# Paulo_V2.net
KiCad netlist of a schematic drawn in EAGLE
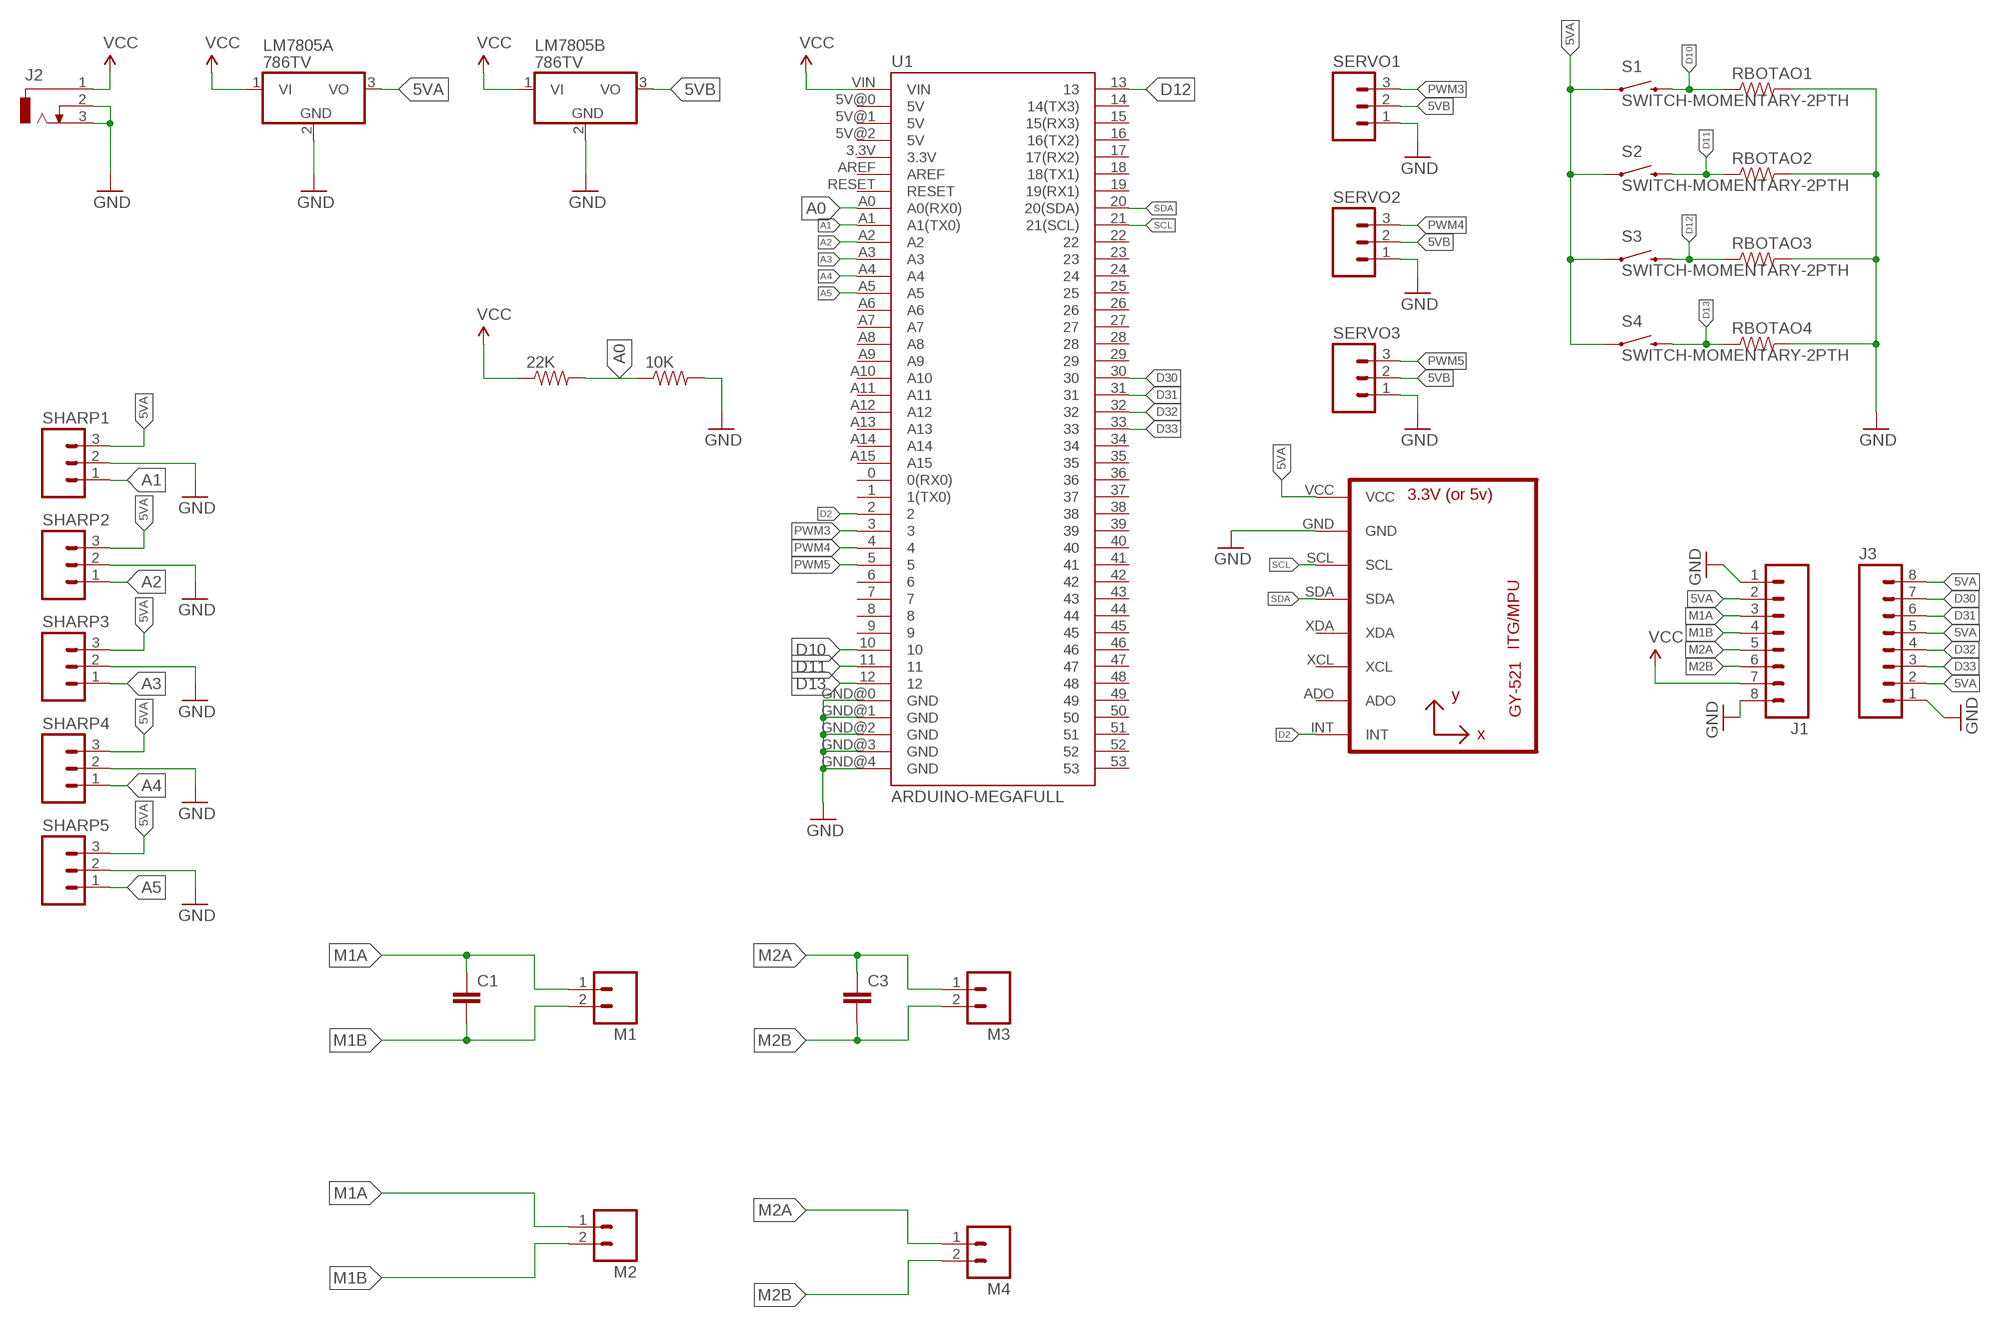
[diagram p0: schematic, sheet 1]

(export (version "E")
  (design (tool "Eeschema 10.0.6"))
  (components
    (comp (ref "10K")
      (value "RESISTOREZ")
      (footprint "eagle-import:AXIAL-0.3EZ")
      (libsource (lib "eagle-import") (part "RESISTOREZ"))
    )
    (comp (ref "22K")
      (value "RESISTOREZ")
      (footprint "eagle-import:AXIAL-0.3EZ")
      (libsource (lib "eagle-import") (part "RESISTOREZ"))
    )
    (comp (ref "C1")
      (value "CAPEZ")
      (footprint "eagle-import:CAP-PTH-SMALLEZ")
      (libsource (lib "eagle-import") (part "CAPEZ"))
    )
    (comp (ref "C3")
      (value "CAPEZ")
      (footprint "eagle-import:CAP-PTH-SMALLEZ")
      (libsource (lib "eagle-import") (part "CAPEZ"))
    )
    (comp (ref "J1")
      (value "M08NO_SILK")
      (footprint "eagle-import:1X08_PIN1_NO_SILK")
      (libsource (lib "eagle-import") (part "M08NO_SILK"))
    )
    (comp (ref "J2")
      (value "DCJ0303")
      (footprint "eagle-import:DCJ0303")
      (libsource (lib "eagle-import") (part "DCJ0303"))
    )
    (comp (ref "J3")
      (value "M08NO_SILK")
      (footprint "eagle-import:1X08_PIN1_NO_SILK")
      (libsource (lib "eagle-import") (part "M08NO_SILK"))
    )
    (comp (ref "LM7805A")
      (value "786TV")
      (footprint "eagle-import:TO220V")
      (libsource (lib "eagle-import") (part "78TV6"))
    )
    (comp (ref "LM7805B")
      (value "786TV")
      (footprint "eagle-import:TO220V")
      (libsource (lib "eagle-import") (part "78TV6"))
    )
    (comp (ref "M1")
      (value "M02JST-PTH-VERT")
      (footprint "eagle-import:JST-2-PTH-VERT")
      (libsource (lib "eagle-import") (part "M02JST-PTH-VERT"))
    )
    (comp (ref "M2")
      (value "M02JST-PTH-VERT")
      (footprint "eagle-import:JST-2-PTH-VERT")
      (libsource (lib "eagle-import") (part "M02JST-PTH-VERT"))
    )
    (comp (ref "M3")
      (value "M02JST-PTH-VERT")
      (footprint "eagle-import:JST-2-PTH-VERT")
      (libsource (lib "eagle-import") (part "M02JST-PTH-VERT"))
    )
    (comp (ref "M4")
      (value "M02JST-PTH-VERT")
      (footprint "eagle-import:JST-2-PTH-VERT")
      (libsource (lib "eagle-import") (part "M02JST-PTH-VERT"))
    )
    (comp (ref "RBOTAO1")
      (value "RESISTOREZ")
      (footprint "eagle-import:AXIAL-0.3EZ")
      (libsource (lib "eagle-import") (part "RESISTOREZ"))
    )
    (comp (ref "RBOTAO2")
      (value "RESISTOREZ")
      (footprint "eagle-import:AXIAL-0.3EZ")
      (libsource (lib "eagle-import") (part "RESISTOREZ"))
    )
    (comp (ref "RBOTAO3")
      (value "RESISTOREZ")
      (footprint "eagle-import:AXIAL-0.3EZ")
      (libsource (lib "eagle-import") (part "RESISTOREZ"))
    )
    (comp (ref "RBOTAO4")
      (value "RESISTOREZ")
      (footprint "eagle-import:AXIAL-0.3EZ")
      (libsource (lib "eagle-import") (part "RESISTOREZ"))
    )
    (comp (ref "S1")
      (value "SWITCH-MOMENTARY-2PTH")
      (footprint "eagle-import:TACTILE-PTH")
      (libsource (lib "eagle-import") (part "SWITCH-MOMENTARY-2PTH"))
    )
    (comp (ref "S2")
      (value "SWITCH-MOMENTARY-2PTH")
      (footprint "eagle-import:TACTILE-PTH")
      (libsource (lib "eagle-import") (part "SWITCH-MOMENTARY-2PTH"))
    )
    (comp (ref "S3")
      (value "SWITCH-MOMENTARY-2PTH")
      (footprint "eagle-import:TACTILE-PTH")
      (libsource (lib "eagle-import") (part "SWITCH-MOMENTARY-2PTH"))
    )
    (comp (ref "S4")
      (value "SWITCH-MOMENTARY-2PTH")
      (footprint "eagle-import:TACTILE-PTH")
      (libsource (lib "eagle-import") (part "SWITCH-MOMENTARY-2PTH"))
    )
    (comp (ref "SERVO1")
      (value "M03LONGPADS")
      (footprint "eagle-import:1X03_LONGPADS")
      (libsource (lib "eagle-import") (part "M03LONGPADS"))
    )
    (comp (ref "SERVO2")
      (value "M03LONGPADS")
      (footprint "eagle-import:1X03_LONGPADS")
      (libsource (lib "eagle-import") (part "M03LONGPADS"))
    )
    (comp (ref "SERVO3")
      (value "M03LONGPADS")
      (footprint "eagle-import:1X03_LONGPADS")
      (libsource (lib "eagle-import") (part "M03LONGPADS"))
    )
    (comp (ref "SHARP1")
      (value "M03LONGPADS")
      (footprint "eagle-import:1X03_LONGPADS")
      (libsource (lib "eagle-import") (part "M03LONGPADS"))
    )
    (comp (ref "SHARP2")
      (value "M03LONGPADS")
      (footprint "eagle-import:1X03_LONGPADS")
      (libsource (lib "eagle-import") (part "M03LONGPADS"))
    )
    (comp (ref "SHARP3")
      (value "M03LONGPADS")
      (footprint "eagle-import:1X03_LONGPADS")
      (libsource (lib "eagle-import") (part "M03LONGPADS"))
    )
    (comp (ref "SHARP4")
      (value "M03LONGPADS")
      (footprint "eagle-import:1X03_LONGPADS")
      (libsource (lib "eagle-import") (part "M03LONGPADS"))
    )
    (comp (ref "SHARP5")
      (value "M03LONGPADS")
      (footprint "eagle-import:1X03_LONGPADS")
      (libsource (lib "eagle-import") (part "M03LONGPADS"))
    )
    (comp (ref "U1")
      (value "ARDUINO-MEGAFULL")
      (footprint "eagle-import:ARDUINO_MEGA")
      (libsource (lib "eagle-import") (part "ARDUINO-MEGAFULL"))
    )
    (comp (ref "U2")
      (value "GY-521MPU6050")
      (footprint "eagle-import:GY-521")
      (libsource (lib "eagle-import") (part "GY-521MPU6050"))
    )
  )
  (nets
    (net (code "1") (name "5VA") (class "Default")
      (node (ref "J1") (pin "2") (pinfunction "2_2") (pintype "passive"))
      (node (ref "J3") (pin "2") (pinfunction "2_2") (pintype "passive"))
      (node (ref "J3") (pin "5") (pinfunction "5_5") (pintype "passive"))
      (node (ref "J3") (pin "8") (pinfunction "8_8") (pintype "passive"))
      (node (ref "LM7805A") (pin "3") (pinfunction "VO_3") (pintype "passive"))
      (node (ref "S1") (pin "1") (pinfunction "1_1") (pintype "passive"))
      (node (ref "S2") (pin "1") (pinfunction "1_1") (pintype "passive"))
      (node (ref "S3") (pin "1") (pinfunction "1_1") (pintype "passive"))
      (node (ref "S4") (pin "1") (pinfunction "1_1") (pintype "passive"))
      (node (ref "SHARP1") (pin "3") (pinfunction "3_3") (pintype "passive"))
      (node (ref "SHARP2") (pin "3") (pinfunction "3_3") (pintype "passive"))
      (node (ref "SHARP3") (pin "3") (pinfunction "3_3") (pintype "passive"))
      (node (ref "SHARP4") (pin "3") (pinfunction "3_3") (pintype "passive"))
      (node (ref "SHARP5") (pin "3") (pinfunction "3_3") (pintype "passive"))
      (node (ref "U2") (pin "VCC") (pinfunction "VCC_VCC") (pintype "bidirectional"))
    )
    (net (code "2") (name "5VB") (class "Default")
      (node (ref "LM7805B") (pin "3") (pinfunction "VO_3") (pintype "passive"))
      (node (ref "SERVO1") (pin "2") (pinfunction "2_2") (pintype "passive"))
      (node (ref "SERVO2") (pin "2") (pinfunction "2_2") (pintype "passive"))
      (node (ref "SERVO3") (pin "2") (pinfunction "2_2") (pintype "passive"))
    )
    (net (code "3") (name "A0") (class "Default")
      (node (ref "10K") (pin "P$1") (pinfunction "1_P$1") (pintype "passive"))
      (node (ref "22K") (pin "P$2") (pinfunction "2_P$2") (pintype "passive"))
      (node (ref "U1") (pin "A0") (pinfunction "A0(RX0)_A0") (pintype "bidirectional"))
    )
    (net (code "4") (name "A1") (class "Default")
      (node (ref "SHARP1") (pin "1") (pinfunction "1_1") (pintype "passive"))
      (node (ref "U1") (pin "A1") (pinfunction "A1(TX0)_A1") (pintype "bidirectional"))
    )
    (net (code "5") (name "A2") (class "Default")
      (node (ref "SHARP2") (pin "1") (pinfunction "1_1") (pintype "passive"))
      (node (ref "U1") (pin "A2") (pinfunction "A2_A2") (pintype "bidirectional"))
    )
    (net (code "6") (name "A3") (class "Default")
      (node (ref "SHARP3") (pin "1") (pinfunction "1_1") (pintype "passive"))
      (node (ref "U1") (pin "A3") (pinfunction "A3_A3") (pintype "bidirectional"))
    )
    (net (code "7") (name "A4") (class "Default")
      (node (ref "SHARP4") (pin "1") (pinfunction "1_1") (pintype "passive"))
      (node (ref "U1") (pin "A4") (pinfunction "A4_A4") (pintype "bidirectional"))
    )
    (net (code "8") (name "A5") (class "Default")
      (node (ref "SHARP5") (pin "1") (pinfunction "1_1") (pintype "passive"))
      (node (ref "U1") (pin "A5") (pinfunction "A5_A5") (pintype "bidirectional"))
    )
    (net (code "9") (name "D2") (class "Default")
      (node (ref "U1") (pin "2") (pinfunction "2_2") (pintype "bidirectional"))
      (node (ref "U2") (pin "INT") (pinfunction "INT_INT") (pintype "bidirectional"))
    )
    (net (code "10") (name "D10") (class "Default")
      (node (ref "RBOTAO1") (pin "P$1") (pinfunction "1_P$1") (pintype "passive"))
      (node (ref "S1") (pin "3") (pinfunction "2_3") (pintype "passive"))
      (node (ref "U1") (pin "10") (pinfunction "10_10") (pintype "bidirectional"))
    )
    (net (code "11") (name "D11") (class "Default")
      (node (ref "RBOTAO2") (pin "P$1") (pinfunction "1_P$1") (pintype "passive"))
      (node (ref "S2") (pin "3") (pinfunction "2_3") (pintype "passive"))
      (node (ref "U1") (pin "11") (pinfunction "11_11") (pintype "bidirectional"))
    )
    (net (code "12") (name "D12") (class "Default")
      (node (ref "RBOTAO3") (pin "P$1") (pinfunction "1_P$1") (pintype "passive"))
      (node (ref "S3") (pin "3") (pinfunction "2_3") (pintype "passive"))
      (node (ref "U1") (pin "13") (pinfunction "13_13") (pintype "bidirectional"))
    )
    (net (code "13") (name "D13") (class "Default")
      (node (ref "RBOTAO4") (pin "P$1") (pinfunction "1_P$1") (pintype "passive"))
      (node (ref "S4") (pin "3") (pinfunction "2_3") (pintype "passive"))
      (node (ref "U1") (pin "12") (pinfunction "12_12") (pintype "bidirectional"))
    )
    (net (code "14") (name "D30") (class "Default")
      (node (ref "J3") (pin "7") (pinfunction "7_7") (pintype "passive"))
      (node (ref "U1") (pin "30") (pinfunction "30_30") (pintype "bidirectional"))
    )
    (net (code "15") (name "D31") (class "Default")
      (node (ref "J3") (pin "6") (pinfunction "6_6") (pintype "passive"))
      (node (ref "U1") (pin "31") (pinfunction "31_31") (pintype "bidirectional"))
    )
    (net (code "16") (name "D32") (class "Default")
      (node (ref "J3") (pin "4") (pinfunction "4_4") (pintype "passive"))
      (node (ref "U1") (pin "32") (pinfunction "32_32") (pintype "bidirectional"))
    )
    (net (code "17") (name "D33") (class "Default")
      (node (ref "J3") (pin "3") (pinfunction "3_3") (pintype "passive"))
      (node (ref "U1") (pin "33") (pinfunction "33_33") (pintype "bidirectional"))
    )
    (net (code "18") (name "GND") (class "Default")
      (node (ref "10K") (pin "P$2") (pinfunction "2_P$2") (pintype "passive"))
      (node (ref "J1") (pin "1") (pinfunction "1_1") (pintype "passive"))
      (node (ref "J1") (pin "8") (pinfunction "8_8") (pintype "passive"))
      (node (ref "J2") (pin "2") (pinfunction "2_2") (pintype "passive"))
      (node (ref "J2") (pin "3") (pinfunction "3_3") (pintype "passive"))
      (node (ref "J3") (pin "1") (pinfunction "1_1") (pintype "passive"))
      (node (ref "LM7805A") (pin "2") (pinfunction "GND_2") (pintype "passive"))
      (node (ref "LM7805B") (pin "2") (pinfunction "GND_2") (pintype "passive"))
      (node (ref "RBOTAO1") (pin "P$2") (pinfunction "2_P$2") (pintype "passive"))
      (node (ref "RBOTAO2") (pin "P$2") (pinfunction "2_P$2") (pintype "passive"))
      (node (ref "RBOTAO3") (pin "P$2") (pinfunction "2_P$2") (pintype "passive"))
      (node (ref "RBOTAO4") (pin "P$2") (pinfunction "2_P$2") (pintype "passive"))
      (node (ref "SERVO1") (pin "1") (pinfunction "1_1") (pintype "passive"))
      (node (ref "SERVO2") (pin "1") (pinfunction "1_1") (pintype "passive"))
      (node (ref "SERVO3") (pin "1") (pinfunction "1_1") (pintype "passive"))
      (node (ref "SHARP1") (pin "2") (pinfunction "2_2") (pintype "passive"))
      (node (ref "SHARP2") (pin "2") (pinfunction "2_2") (pintype "passive"))
      (node (ref "SHARP3") (pin "2") (pinfunction "2_2") (pintype "passive"))
      (node (ref "SHARP4") (pin "2") (pinfunction "2_2") (pintype "passive"))
      (node (ref "SHARP5") (pin "2") (pinfunction "2_2") (pintype "passive"))
      (node (ref "U1") (pin "GND@0") (pinfunction "GND_GND@0") (pintype "bidirectional"))
      (node (ref "U1") (pin "GND@1") (pinfunction "GND_GND@1") (pintype "bidirectional"))
      (node (ref "U1") (pin "GND@2") (pinfunction "GND_GND@2") (pintype "bidirectional"))
      (node (ref "U1") (pin "GND@3") (pinfunction "GND_GND@3") (pintype "bidirectional"))
      (node (ref "U1") (pin "GND@4") (pinfunction "GND_GND@4") (pintype "bidirectional"))
      (node (ref "U2") (pin "GND") (pinfunction "GND_GND") (pintype "bidirectional"))
    )
    (net (code "19") (name "M1A") (class "Default")
      (node (ref "C1") (pin "1") (pinfunction "1_1") (pintype "passive"))
      (node (ref "J1") (pin "3") (pinfunction "3_3") (pintype "passive"))
      (node (ref "M1") (pin "1") (pinfunction "1_1") (pintype "passive"))
      (node (ref "M2") (pin "1") (pinfunction "1_1") (pintype "passive"))
    )
    (net (code "20") (name "M1B") (class "Default")
      (node (ref "C1") (pin "2") (pinfunction "2_2") (pintype "passive"))
      (node (ref "J1") (pin "4") (pinfunction "4_4") (pintype "passive"))
      (node (ref "M1") (pin "2") (pinfunction "2_2") (pintype "passive"))
      (node (ref "M2") (pin "2") (pinfunction "2_2") (pintype "passive"))
    )
    (net (code "21") (name "M2A") (class "Default")
      (node (ref "C3") (pin "1") (pinfunction "1_1") (pintype "passive"))
      (node (ref "J1") (pin "5") (pinfunction "5_5") (pintype "passive"))
      (node (ref "M3") (pin "1") (pinfunction "1_1") (pintype "passive"))
      (node (ref "M4") (pin "1") (pinfunction "1_1") (pintype "passive"))
    )
    (net (code "22") (name "M2B") (class "Default")
      (node (ref "C3") (pin "2") (pinfunction "2_2") (pintype "passive"))
      (node (ref "J1") (pin "6") (pinfunction "6_6") (pintype "passive"))
      (node (ref "M3") (pin "2") (pinfunction "2_2") (pintype "passive"))
      (node (ref "M4") (pin "2") (pinfunction "2_2") (pintype "passive"))
    )
    (net (code "23") (name "PWM3") (class "Default")
      (node (ref "SERVO1") (pin "3") (pinfunction "3_3") (pintype "passive"))
      (node (ref "U1") (pin "3") (pinfunction "3_3") (pintype "bidirectional"))
    )
    (net (code "24") (name "PWM4") (class "Default")
      (node (ref "SERVO2") (pin "3") (pinfunction "3_3") (pintype "passive"))
      (node (ref "U1") (pin "4") (pinfunction "4_4") (pintype "bidirectional"))
    )
    (net (code "25") (name "PWM5") (class "Default")
      (node (ref "SERVO3") (pin "3") (pinfunction "3_3") (pintype "passive"))
      (node (ref "U1") (pin "5") (pinfunction "5_5") (pintype "bidirectional"))
    )
    (net (code "26") (name "SCL") (class "Default")
      (node (ref "U1") (pin "21") (pinfunction "21(SCL)_21") (pintype "bidirectional"))
      (node (ref "U2") (pin "SCL") (pinfunction "SCL_SCL") (pintype "bidirectional"))
    )
    (net (code "27") (name "SDA") (class "Default")
      (node (ref "U1") (pin "20") (pinfunction "20(SDA)_20") (pintype "bidirectional"))
      (node (ref "U2") (pin "SDA") (pinfunction "SDA_SDA") (pintype "bidirectional"))
    )
    (net (code "28") (name "VCC") (class "Default")
      (node (ref "22K") (pin "P$1") (pinfunction "1_P$1") (pintype "passive"))
      (node (ref "J1") (pin "7") (pinfunction "7_7") (pintype "passive"))
      (node (ref "J2") (pin "1") (pinfunction "1_1") (pintype "passive"))
      (node (ref "LM7805A") (pin "1") (pinfunction "VI_1") (pintype "input"))
      (node (ref "LM7805B") (pin "1") (pinfunction "VI_1") (pintype "input"))
      (node (ref "U1") (pin "VIN") (pinfunction "VIN_VIN") (pintype "bidirectional"))
    )
    (net (code "29") (name "unconnected-(U1-0(RX0)-Pad0)") (class "Default")
      (node (ref "U1") (pin "0") (pinfunction "0(RX0)_0") (pintype "bidirectional"))
    )
    (net (code "30") (name "unconnected-(U1-1(TX0)-Pad1)") (class "Default")
      (node (ref "U1") (pin "1") (pinfunction "1(TX0)_1") (pintype "bidirectional"))
    )
    (net (code "31") (name "unconnected-(U1-5V-Pad5V@0)") (class "Default")
      (node (ref "U1") (pin "5V@0") (pinfunction "5V_5V@0") (pintype "bidirectional"))
    )
    (net (code "32") (name "unconnected-(U1-5V-Pad5V@1)") (class "Default")
      (node (ref "U1") (pin "5V@1") (pinfunction "5V_5V@1") (pintype "bidirectional"))
    )
    (net (code "33") (name "unconnected-(U1-5V-Pad5V@2)") (class "Default")
      (node (ref "U1") (pin "5V@2") (pinfunction "5V_5V@2") (pintype "bidirectional"))
    )
    (net (code "34") (name "unconnected-(U1-14(TX3)-Pad14)") (class "Default")
      (node (ref "U1") (pin "14") (pinfunction "14(TX3)_14") (pintype "bidirectional"))
    )
    (net (code "35") (name "unconnected-(U1-15(RX3)-Pad15)") (class "Default")
      (node (ref "U1") (pin "15") (pinfunction "15(RX3)_15") (pintype "bidirectional"))
    )
    (net (code "36") (name "unconnected-(U1-16(TX2)-Pad16)") (class "Default")
      (node (ref "U1") (pin "16") (pinfunction "16(TX2)_16") (pintype "bidirectional"))
    )
    (net (code "37") (name "unconnected-(U1-17(RX2)-Pad17)") (class "Default")
      (node (ref "U1") (pin "17") (pinfunction "17(RX2)_17") (pintype "bidirectional"))
    )
    (net (code "38") (name "unconnected-(U1-18(TX1)-Pad18)") (class "Default")
      (node (ref "U1") (pin "18") (pinfunction "18(TX1)_18") (pintype "bidirectional"))
    )
    (net (code "39") (name "unconnected-(U1-19(RX1)-Pad19)") (class "Default")
      (node (ref "U1") (pin "19") (pinfunction "19(RX1)_19") (pintype "bidirectional"))
    )
    (net (code "40") (name "unconnected-(U1-Pad3.3V)") (class "Default")
      (node (ref "U1") (pin "3.3V") (pinfunction "3.3V_3.3V") (pintype "bidirectional"))
    )
    (net (code "41") (name "unconnected-(U1-Pad6)") (class "Default")
      (node (ref "U1") (pin "6") (pinfunction "6_6") (pintype "bidirectional"))
    )
    (net (code "42") (name "unconnected-(U1-Pad7)") (class "Default")
      (node (ref "U1") (pin "7") (pinfunction "7_7") (pintype "bidirectional"))
    )
    (net (code "43") (name "unconnected-(U1-Pad8)") (class "Default")
      (node (ref "U1") (pin "8") (pinfunction "8_8") (pintype "bidirectional"))
    )
    (net (code "44") (name "unconnected-(U1-Pad9)") (class "Default")
      (node (ref "U1") (pin "9") (pinfunction "9_9") (pintype "bidirectional"))
    )
    (net (code "45") (name "unconnected-(U1-Pad22)") (class "Default")
      (node (ref "U1") (pin "22") (pinfunction "22_22") (pintype "bidirectional"))
    )
    (net (code "46") (name "unconnected-(U1-Pad23)") (class "Default")
      (node (ref "U1") (pin "23") (pinfunction "23_23") (pintype "bidirectional"))
    )
    (net (code "47") (name "unconnected-(U1-Pad24)") (class "Default")
      (node (ref "U1") (pin "24") (pinfunction "24_24") (pintype "bidirectional"))
    )
    (net (code "48") (name "unconnected-(U1-Pad25)") (class "Default")
      (node (ref "U1") (pin "25") (pinfunction "25_25") (pintype "bidirectional"))
    )
    (net (code "49") (name "unconnected-(U1-Pad26)") (class "Default")
      (node (ref "U1") (pin "26") (pinfunction "26_26") (pintype "bidirectional"))
    )
    (net (code "50") (name "unconnected-(U1-Pad27)") (class "Default")
      (node (ref "U1") (pin "27") (pinfunction "27_27") (pintype "bidirectional"))
    )
    (net (code "51") (name "unconnected-(U1-Pad28)") (class "Default")
      (node (ref "U1") (pin "28") (pinfunction "28_28") (pintype "bidirectional"))
    )
    (net (code "52") (name "unconnected-(U1-Pad29)") (class "Default")
      (node (ref "U1") (pin "29") (pinfunction "29_29") (pintype "bidirectional"))
    )
    (net (code "53") (name "unconnected-(U1-Pad34)") (class "Default")
      (node (ref "U1") (pin "34") (pinfunction "34_34") (pintype "bidirectional"))
    )
    (net (code "54") (name "unconnected-(U1-Pad35)") (class "Default")
      (node (ref "U1") (pin "35") (pinfunction "35_35") (pintype "bidirectional"))
    )
    (net (code "55") (name "unconnected-(U1-Pad36)") (class "Default")
      (node (ref "U1") (pin "36") (pinfunction "36_36") (pintype "bidirectional"))
    )
    (net (code "56") (name "unconnected-(U1-Pad37)") (class "Default")
      (node (ref "U1") (pin "37") (pinfunction "37_37") (pintype "bidirectional"))
    )
    (net (code "57") (name "unconnected-(U1-Pad38)") (class "Default")
      (node (ref "U1") (pin "38") (pinfunction "38_38") (pintype "bidirectional"))
    )
    (net (code "58") (name "unconnected-(U1-Pad39)") (class "Default")
      (node (ref "U1") (pin "39") (pinfunction "39_39") (pintype "bidirectional"))
    )
    (net (code "59") (name "unconnected-(U1-Pad40)") (class "Default")
      (node (ref "U1") (pin "40") (pinfunction "40_40") (pintype "bidirectional"))
    )
    (net (code "60") (name "unconnected-(U1-Pad41)") (class "Default")
      (node (ref "U1") (pin "41") (pinfunction "41_41") (pintype "bidirectional"))
    )
    (net (code "61") (name "unconnected-(U1-Pad42)") (class "Default")
      (node (ref "U1") (pin "42") (pinfunction "42_42") (pintype "bidirectional"))
    )
    (net (code "62") (name "unconnected-(U1-Pad43)") (class "Default")
      (node (ref "U1") (pin "43") (pinfunction "43_43") (pintype "bidirectional"))
    )
    (net (code "63") (name "unconnected-(U1-Pad44)") (class "Default")
      (node (ref "U1") (pin "44") (pinfunction "44_44") (pintype "bidirectional"))
    )
    (net (code "64") (name "unconnected-(U1-Pad45)") (class "Default")
      (node (ref "U1") (pin "45") (pinfunction "45_45") (pintype "bidirectional"))
    )
    (net (code "65") (name "unconnected-(U1-Pad46)") (class "Default")
      (node (ref "U1") (pin "46") (pinfunction "46_46") (pintype "bidirectional"))
    )
    (net (code "66") (name "unconnected-(U1-Pad47)") (class "Default")
      (node (ref "U1") (pin "47") (pinfunction "47_47") (pintype "bidirectional"))
    )
    (net (code "67") (name "unconnected-(U1-Pad48)") (class "Default")
      (node (ref "U1") (pin "48") (pinfunction "48_48") (pintype "bidirectional"))
    )
    (net (code "68") (name "unconnected-(U1-Pad49)") (class "Default")
      (node (ref "U1") (pin "49") (pinfunction "49_49") (pintype "bidirectional"))
    )
    (net (code "69") (name "unconnected-(U1-Pad50)") (class "Default")
      (node (ref "U1") (pin "50") (pinfunction "50_50") (pintype "bidirectional"))
    )
    (net (code "70") (name "unconnected-(U1-Pad51)") (class "Default")
      (node (ref "U1") (pin "51") (pinfunction "51_51") (pintype "bidirectional"))
    )
    (net (code "71") (name "unconnected-(U1-Pad52)") (class "Default")
      (node (ref "U1") (pin "52") (pinfunction "52_52") (pintype "bidirectional"))
    )
    (net (code "72") (name "unconnected-(U1-Pad53)") (class "Default")
      (node (ref "U1") (pin "53") (pinfunction "53_53") (pintype "bidirectional"))
    )
    (net (code "73") (name "unconnected-(U1-PadA6)") (class "Default")
      (node (ref "U1") (pin "A6") (pinfunction "A6_A6") (pintype "bidirectional"))
    )
    (net (code "74") (name "unconnected-(U1-PadA7)") (class "Default")
      (node (ref "U1") (pin "A7") (pinfunction "A7_A7") (pintype "bidirectional"))
    )
    (net (code "75") (name "unconnected-(U1-PadA8)") (class "Default")
      (node (ref "U1") (pin "A8") (pinfunction "A8_A8") (pintype "bidirectional"))
    )
    (net (code "76") (name "unconnected-(U1-PadA9)") (class "Default")
      (node (ref "U1") (pin "A9") (pinfunction "A9_A9") (pintype "bidirectional"))
    )
    (net (code "77") (name "unconnected-(U1-PadA10)") (class "Default")
      (node (ref "U1") (pin "A10") (pinfunction "A10_A10") (pintype "bidirectional"))
    )
    (net (code "78") (name "unconnected-(U1-PadA11)") (class "Default")
      (node (ref "U1") (pin "A11") (pinfunction "A11_A11") (pintype "bidirectional"))
    )
    (net (code "79") (name "unconnected-(U1-PadA12)") (class "Default")
      (node (ref "U1") (pin "A12") (pinfunction "A12_A12") (pintype "bidirectional"))
    )
    (net (code "80") (name "unconnected-(U1-PadA13)") (class "Default")
      (node (ref "U1") (pin "A13") (pinfunction "A13_A13") (pintype "bidirectional"))
    )
    (net (code "81") (name "unconnected-(U1-PadA14)") (class "Default")
      (node (ref "U1") (pin "A14") (pinfunction "A14_A14") (pintype "bidirectional"))
    )
    (net (code "82") (name "unconnected-(U1-PadA15)") (class "Default")
      (node (ref "U1") (pin "A15") (pinfunction "A15_A15") (pintype "bidirectional"))
    )
    (net (code "83") (name "unconnected-(U1-PadAREF)") (class "Default")
      (node (ref "U1") (pin "AREF") (pinfunction "AREF_AREF") (pintype "bidirectional"))
    )
    (net (code "84") (name "unconnected-(U1-PadRESET)") (class "Default")
      (node (ref "U1") (pin "RESET") (pinfunction "RESET_RESET") (pintype "bidirectional"))
    )
    (net (code "85") (name "unconnected-(U2-PadADO)") (class "Default")
      (node (ref "U2") (pin "ADO") (pinfunction "ADO_ADO") (pintype "bidirectional"))
    )
    (net (code "86") (name "unconnected-(U2-PadXCL)") (class "Default")
      (node (ref "U2") (pin "XCL") (pinfunction "XCL_XCL") (pintype "bidirectional"))
    )
    (net (code "87") (name "unconnected-(U2-PadXDA)") (class "Default")
      (node (ref "U2") (pin "XDA") (pinfunction "XDA_XDA") (pintype "bidirectional"))
    )
  )
)
